# 3DAG_V2.net
KiCad netlist of a schematic drawn in EAGLE
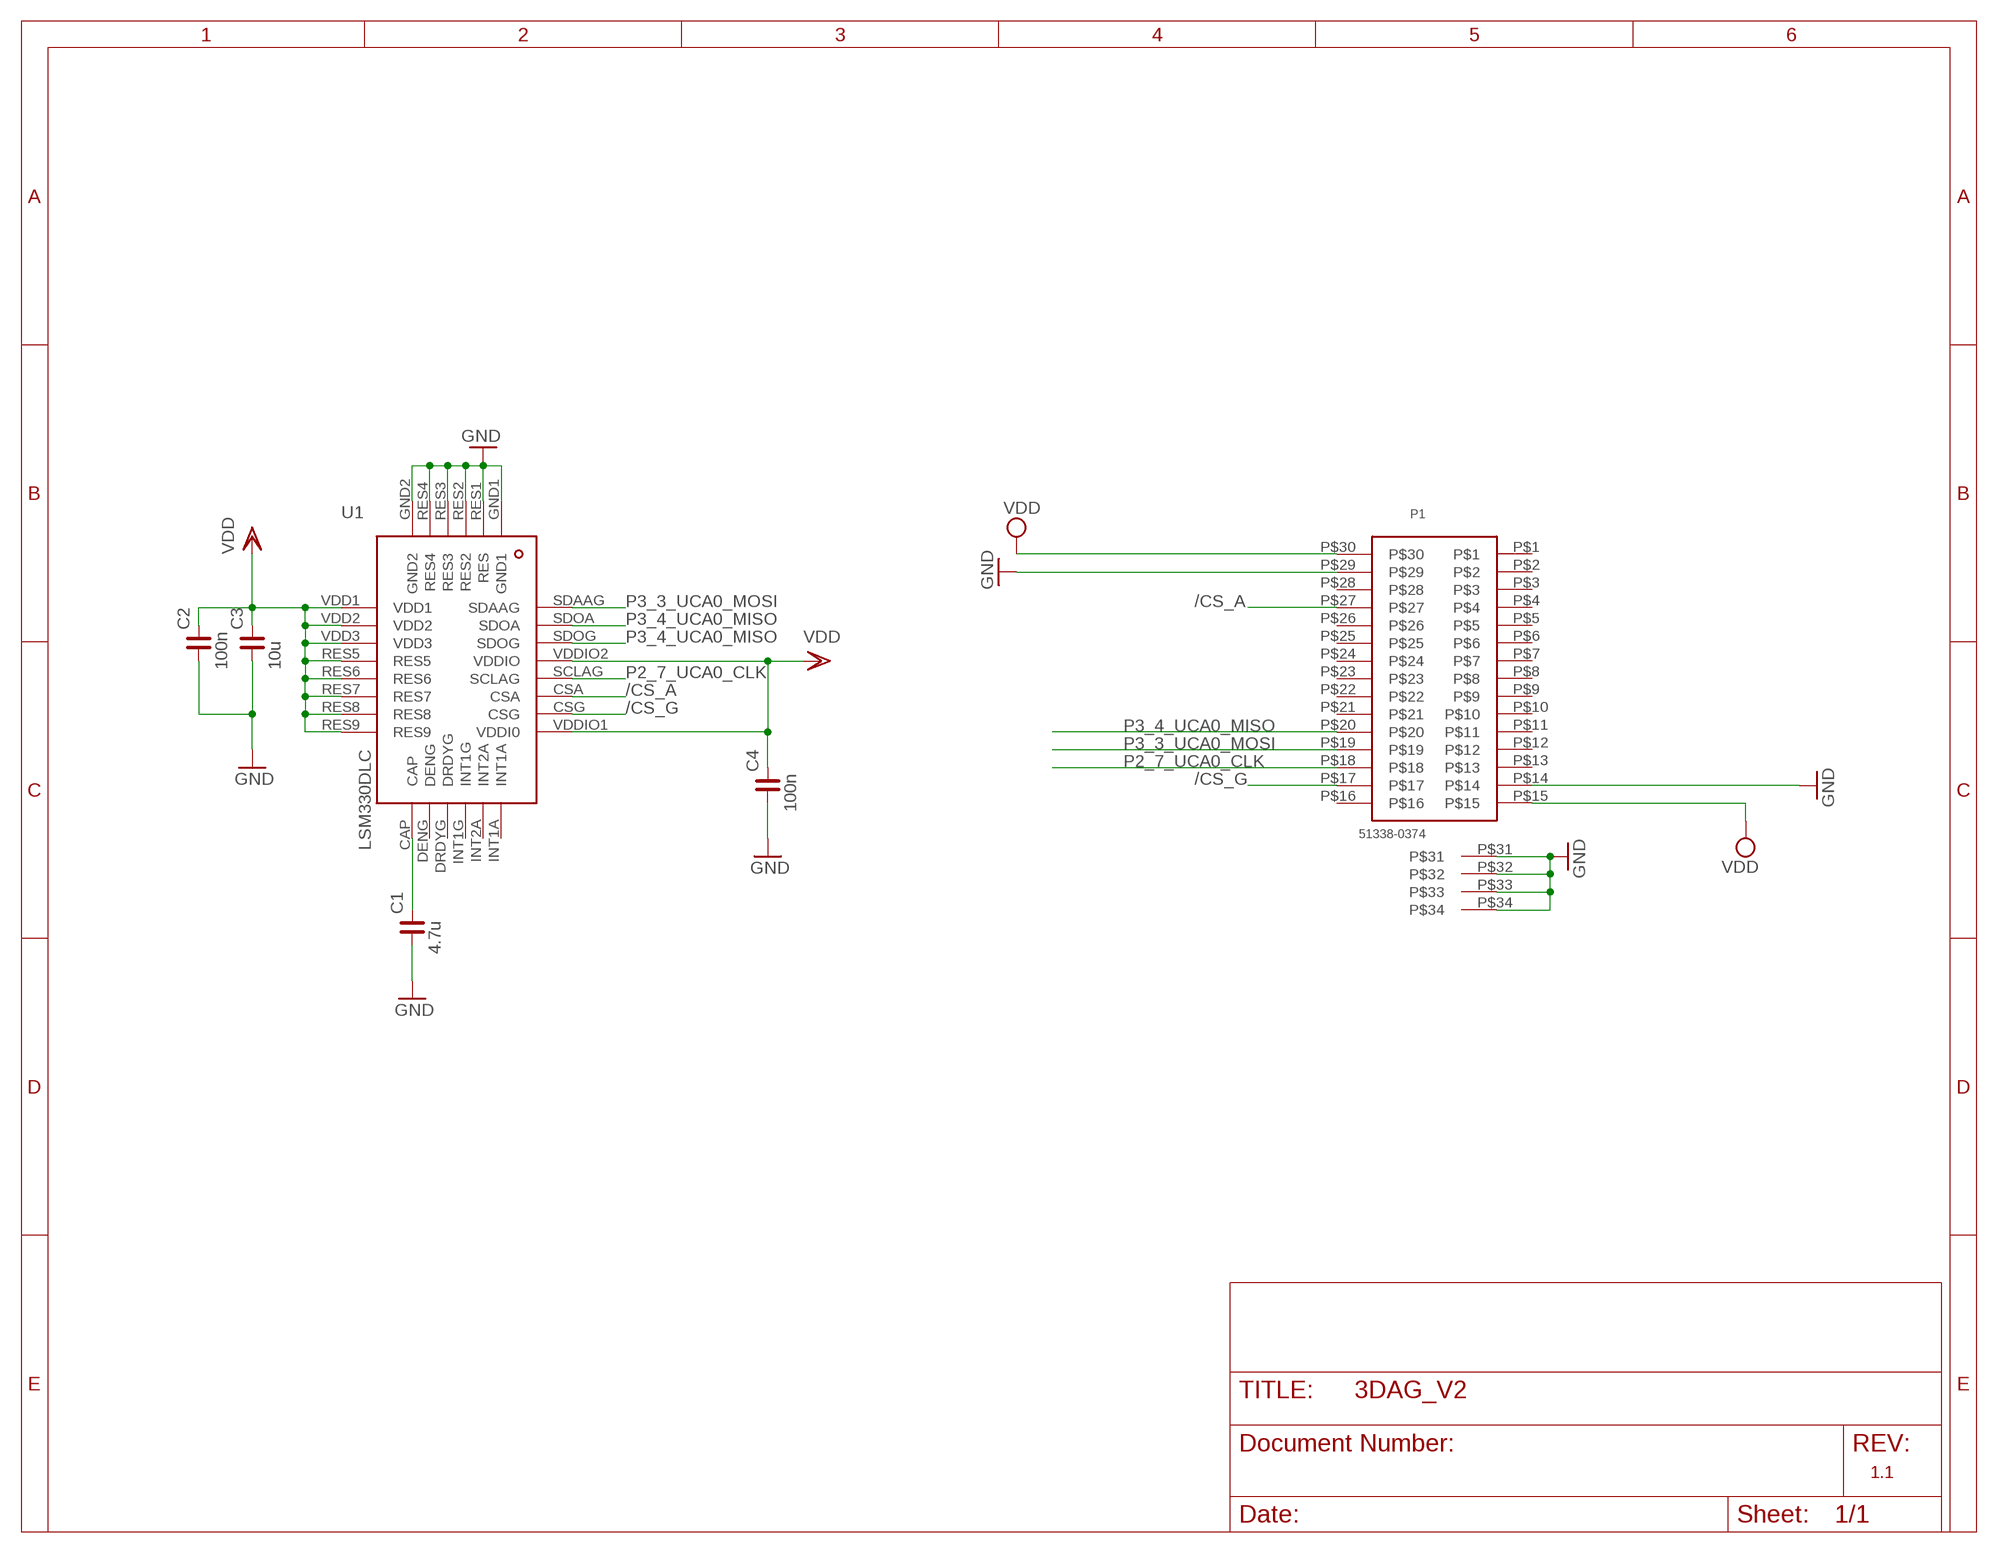
[diagram p0: schematic, sheet 1]

(export (version "E")
  (design (tool "Eeschema 10.0.6"))
  (components
    (comp (ref "C1")
      (value "4.7u")
      (footprint "eagle-import:C0402")
      (libsource (lib "eagle-import") (part "C_0402"))
    )
    (comp (ref "C2")
      (value "100n")
      (footprint "eagle-import:C0402")
      (libsource (lib "eagle-import") (part "C_0402"))
    )
    (comp (ref "C3")
      (value "10u")
      (footprint "eagle-import:C0402")
      (libsource (lib "eagle-import") (part "C_0402"))
    )
    (comp (ref "C4")
      (value "100n")
      (footprint "eagle-import:C0402")
      (libsource (lib "eagle-import") (part "C_0402"))
    )
    (comp (ref "P1")
      (value "51338-0374")
      (footprint "eagle-import:51338-0374_RECEPTACLE")
      (libsource (lib "eagle-import") (part "51338-0374_RECEPTACLE"))
    )
    (comp (ref "U$4")
      (value "LSM330DLC")
      (footprint "eagle-import:LSM330DLC")
      (libsource (lib "eagle-import") (part "LSM330DLC"))
    )
  )
  (nets
    (net (code "1") (name "/P2_7_UCA0_CLK") (class "Default")
      (node (ref "P1") (pin "P$18") (pinfunction "P$18_P$18") (pintype "bidirectional"))
      (node (ref "U$4") (pin "SCLAG") (pinfunction "SCLAG_SCLAG") (pintype "input"))
    )
    (net (code "2") (name "/P3_3_UCA0_MOSI") (class "Default")
      (node (ref "P1") (pin "P$19") (pinfunction "P$19_P$19") (pintype "bidirectional"))
      (node (ref "U$4") (pin "SDAAG") (pinfunction "SDAAG_SDAAG") (pintype "bidirectional"))
    )
    (net (code "3") (name "/P3_4_UCA0_MISO") (class "Default")
      (node (ref "P1") (pin "P$20") (pinfunction "P$20_P$20") (pintype "bidirectional"))
      (node (ref "U$4") (pin "SDOA") (pinfunction "SDOA_SDOA") (pintype "bidirectional"))
      (node (ref "U$4") (pin "SDOG") (pinfunction "SDOG_SDOG") (pintype "bidirectional"))
    )
    (net (code "4") (name "/{slash}CS_A") (class "Default")
      (node (ref "P1") (pin "P$27") (pinfunction "P$27_P$27") (pintype "bidirectional"))
      (node (ref "U$4") (pin "CSA") (pinfunction "CSA_CSA") (pintype "input"))
    )
    (net (code "5") (name "/{slash}CS_G") (class "Default")
      (node (ref "P1") (pin "P$17") (pinfunction "P$17_P$17") (pintype "bidirectional"))
      (node (ref "U$4") (pin "CSG") (pinfunction "CSG_CSG") (pintype "input"))
    )
    (net (code "6") (name "GND") (class "Default")
      (node (ref "C1") (pin "1") (pinfunction "1_1") (pintype "passive"))
      (node (ref "C2") (pin "1") (pinfunction "1_1") (pintype "passive"))
      (node (ref "C3") (pin "1") (pinfunction "1_1") (pintype "passive"))
      (node (ref "C4") (pin "1") (pinfunction "1_1") (pintype "passive"))
      (node (ref "P1") (pin "P$14") (pinfunction "P$14_P$14") (pintype "bidirectional"))
      (node (ref "P1") (pin "P$29") (pinfunction "P$29_P$29") (pintype "bidirectional"))
      (node (ref "P1") (pin "P$31") (pinfunction "P$31_P$31") (pintype "bidirectional"))
      (node (ref "P1") (pin "P$32") (pinfunction "P$32_P$32") (pintype "bidirectional"))
      (node (ref "P1") (pin "P$33") (pinfunction "P$33_P$33") (pintype "bidirectional"))
      (node (ref "P1") (pin "P$34") (pinfunction "P$34_P$34") (pintype "bidirectional"))
      (node (ref "U$4") (pin "GND1") (pinfunction "GND1_GND1") (pintype "power_in"))
      (node (ref "U$4") (pin "GND2") (pinfunction "GND2_GND2") (pintype "power_in"))
      (node (ref "U$4") (pin "RES1") (pinfunction "RES_RES1") (pintype "power_in"))
      (node (ref "U$4") (pin "RES2") (pinfunction "RES2_RES2") (pintype "power_in"))
      (node (ref "U$4") (pin "RES3") (pinfunction "RES3_RES3") (pintype "bidirectional"))
      (node (ref "U$4") (pin "RES4") (pinfunction "RES4_RES4") (pintype "bidirectional"))
    )
    (net (code "7") (name "Net-(C1-Pad2)") (class "Default")
      (node (ref "C1") (pin "2") (pinfunction "2_2") (pintype "passive"))
      (node (ref "U$4") (pin "CAP") (pinfunction "CAP_CAP") (pintype "passive"))
    )
    (net (code "8") (name "VDD") (class "Default")
      (node (ref "C2") (pin "2") (pinfunction "2_2") (pintype "passive"))
      (node (ref "C3") (pin "2") (pinfunction "2_2") (pintype "passive"))
      (node (ref "C4") (pin "2") (pinfunction "2_2") (pintype "passive"))
      (node (ref "P1") (pin "P$15") (pinfunction "P$15_P$15") (pintype "bidirectional"))
      (node (ref "P1") (pin "P$30") (pinfunction "P$30_P$30") (pintype "bidirectional"))
      (node (ref "U$4") (pin "RES5") (pinfunction "RES5_RES5") (pintype "bidirectional"))
      (node (ref "U$4") (pin "RES6") (pinfunction "RES6_RES6") (pintype "bidirectional"))
      (node (ref "U$4") (pin "RES7") (pinfunction "RES7_RES7") (pintype "bidirectional"))
      (node (ref "U$4") (pin "RES8") (pinfunction "RES8_RES8") (pintype "bidirectional"))
      (node (ref "U$4") (pin "RES9") (pinfunction "RES9_RES9") (pintype "bidirectional"))
      (node (ref "U$4") (pin "VDD1") (pinfunction "VDD1_VDD1") (pintype "power_in"))
      (node (ref "U$4") (pin "VDD2") (pinfunction "VDD2_VDD2") (pintype "power_in"))
      (node (ref "U$4") (pin "VDD3") (pinfunction "VDD3_VDD3") (pintype "power_in"))
      (node (ref "U$4") (pin "VDDIO1") (pinfunction "VDDI0_VDDIO1") (pintype "power_in"))
      (node (ref "U$4") (pin "VDDIO2") (pinfunction "VDDIO_VDDIO2") (pintype "power_in"))
    )
    (net (code "9") (name "unconnected-(P1-PadP$1)") (class "Default")
      (node (ref "P1") (pin "P$1") (pinfunction "P$1_P$1") (pintype "bidirectional"))
    )
    (net (code "10") (name "unconnected-(P1-PadP$2)") (class "Default")
      (node (ref "P1") (pin "P$2") (pinfunction "P$2_P$2") (pintype "bidirectional"))
    )
    (net (code "11") (name "unconnected-(P1-PadP$3)") (class "Default")
      (node (ref "P1") (pin "P$3") (pinfunction "P$3_P$3") (pintype "bidirectional"))
    )
    (net (code "12") (name "unconnected-(P1-PadP$4)") (class "Default")
      (node (ref "P1") (pin "P$4") (pinfunction "P$4_P$4") (pintype "bidirectional"))
    )
    (net (code "13") (name "unconnected-(P1-PadP$5)") (class "Default")
      (node (ref "P1") (pin "P$5") (pinfunction "P$5_P$5") (pintype "bidirectional"))
    )
    (net (code "14") (name "unconnected-(P1-PadP$6)") (class "Default")
      (node (ref "P1") (pin "P$6") (pinfunction "P$6_P$6") (pintype "bidirectional"))
    )
    (net (code "15") (name "unconnected-(P1-PadP$7)") (class "Default")
      (node (ref "P1") (pin "P$7") (pinfunction "P$7_P$7") (pintype "bidirectional"))
    )
    (net (code "16") (name "unconnected-(P1-PadP$8)") (class "Default")
      (node (ref "P1") (pin "P$8") (pinfunction "P$8_P$8") (pintype "bidirectional"))
    )
    (net (code "17") (name "unconnected-(P1-PadP$9)") (class "Default")
      (node (ref "P1") (pin "P$9") (pinfunction "P$9_P$9") (pintype "bidirectional"))
    )
    (net (code "18") (name "unconnected-(P1-PadP$10)") (class "Default")
      (node (ref "P1") (pin "P$10") (pinfunction "P$10_P$10") (pintype "bidirectional"))
    )
    (net (code "19") (name "unconnected-(P1-PadP$11)") (class "Default")
      (node (ref "P1") (pin "P$11") (pinfunction "P$11_P$11") (pintype "bidirectional"))
    )
    (net (code "20") (name "unconnected-(P1-PadP$12)") (class "Default")
      (node (ref "P1") (pin "P$12") (pinfunction "P$12_P$12") (pintype "bidirectional"))
    )
    (net (code "21") (name "unconnected-(P1-PadP$13)") (class "Default")
      (node (ref "P1") (pin "P$13") (pinfunction "P$13_P$13") (pintype "bidirectional"))
    )
    (net (code "22") (name "unconnected-(P1-PadP$16)") (class "Default")
      (node (ref "P1") (pin "P$16") (pinfunction "P$16_P$16") (pintype "bidirectional"))
    )
    (net (code "23") (name "unconnected-(P1-PadP$21)") (class "Default")
      (node (ref "P1") (pin "P$21") (pinfunction "P$21_P$21") (pintype "bidirectional"))
    )
    (net (code "24") (name "unconnected-(P1-PadP$22)") (class "Default")
      (node (ref "P1") (pin "P$22") (pinfunction "P$22_P$22") (pintype "bidirectional"))
    )
    (net (code "25") (name "unconnected-(P1-PadP$23)") (class "Default")
      (node (ref "P1") (pin "P$23") (pinfunction "P$23_P$23") (pintype "bidirectional"))
    )
    (net (code "26") (name "unconnected-(P1-PadP$24)") (class "Default")
      (node (ref "P1") (pin "P$24") (pinfunction "P$24_P$24") (pintype "bidirectional"))
    )
    (net (code "27") (name "unconnected-(P1-PadP$25)") (class "Default")
      (node (ref "P1") (pin "P$25") (pinfunction "P$25_P$25") (pintype "bidirectional"))
    )
    (net (code "28") (name "unconnected-(P1-PadP$26)") (class "Default")
      (node (ref "P1") (pin "P$26") (pinfunction "P$26_P$26") (pintype "bidirectional"))
    )
    (net (code "29") (name "unconnected-(P1-PadP$28)") (class "Default")
      (node (ref "P1") (pin "P$28") (pinfunction "P$28_P$28") (pintype "bidirectional"))
    )
    (net (code "30") (name "unconnected-(U$4-PadDENG)") (class "Default")
      (node (ref "U$4") (pin "DENG") (pinfunction "DENG_DENG") (pintype "input"))
    )
    (net (code "31") (name "unconnected-(U$4-PadDRDYG)") (class "Default")
      (node (ref "U$4") (pin "DRDYG") (pinfunction "DRDYG_DRDYG") (pintype "output"))
    )
    (net (code "32") (name "unconnected-(U$4-PadINT1A)") (class "Default")
      (node (ref "U$4") (pin "INT1A") (pinfunction "INT1A_INT1A") (pintype "output"))
    )
    (net (code "33") (name "unconnected-(U$4-PadINT1G)") (class "Default")
      (node (ref "U$4") (pin "INT1G") (pinfunction "INT1G_INT1G") (pintype "output"))
    )
    (net (code "34") (name "unconnected-(U$4-PadINT2A)") (class "Default")
      (node (ref "U$4") (pin "INT2A") (pinfunction "INT2A_INT2A") (pintype "output"))
    )
  )
)
